# gnode.net
KiCad netlist of a schematic drawn in EAGLE
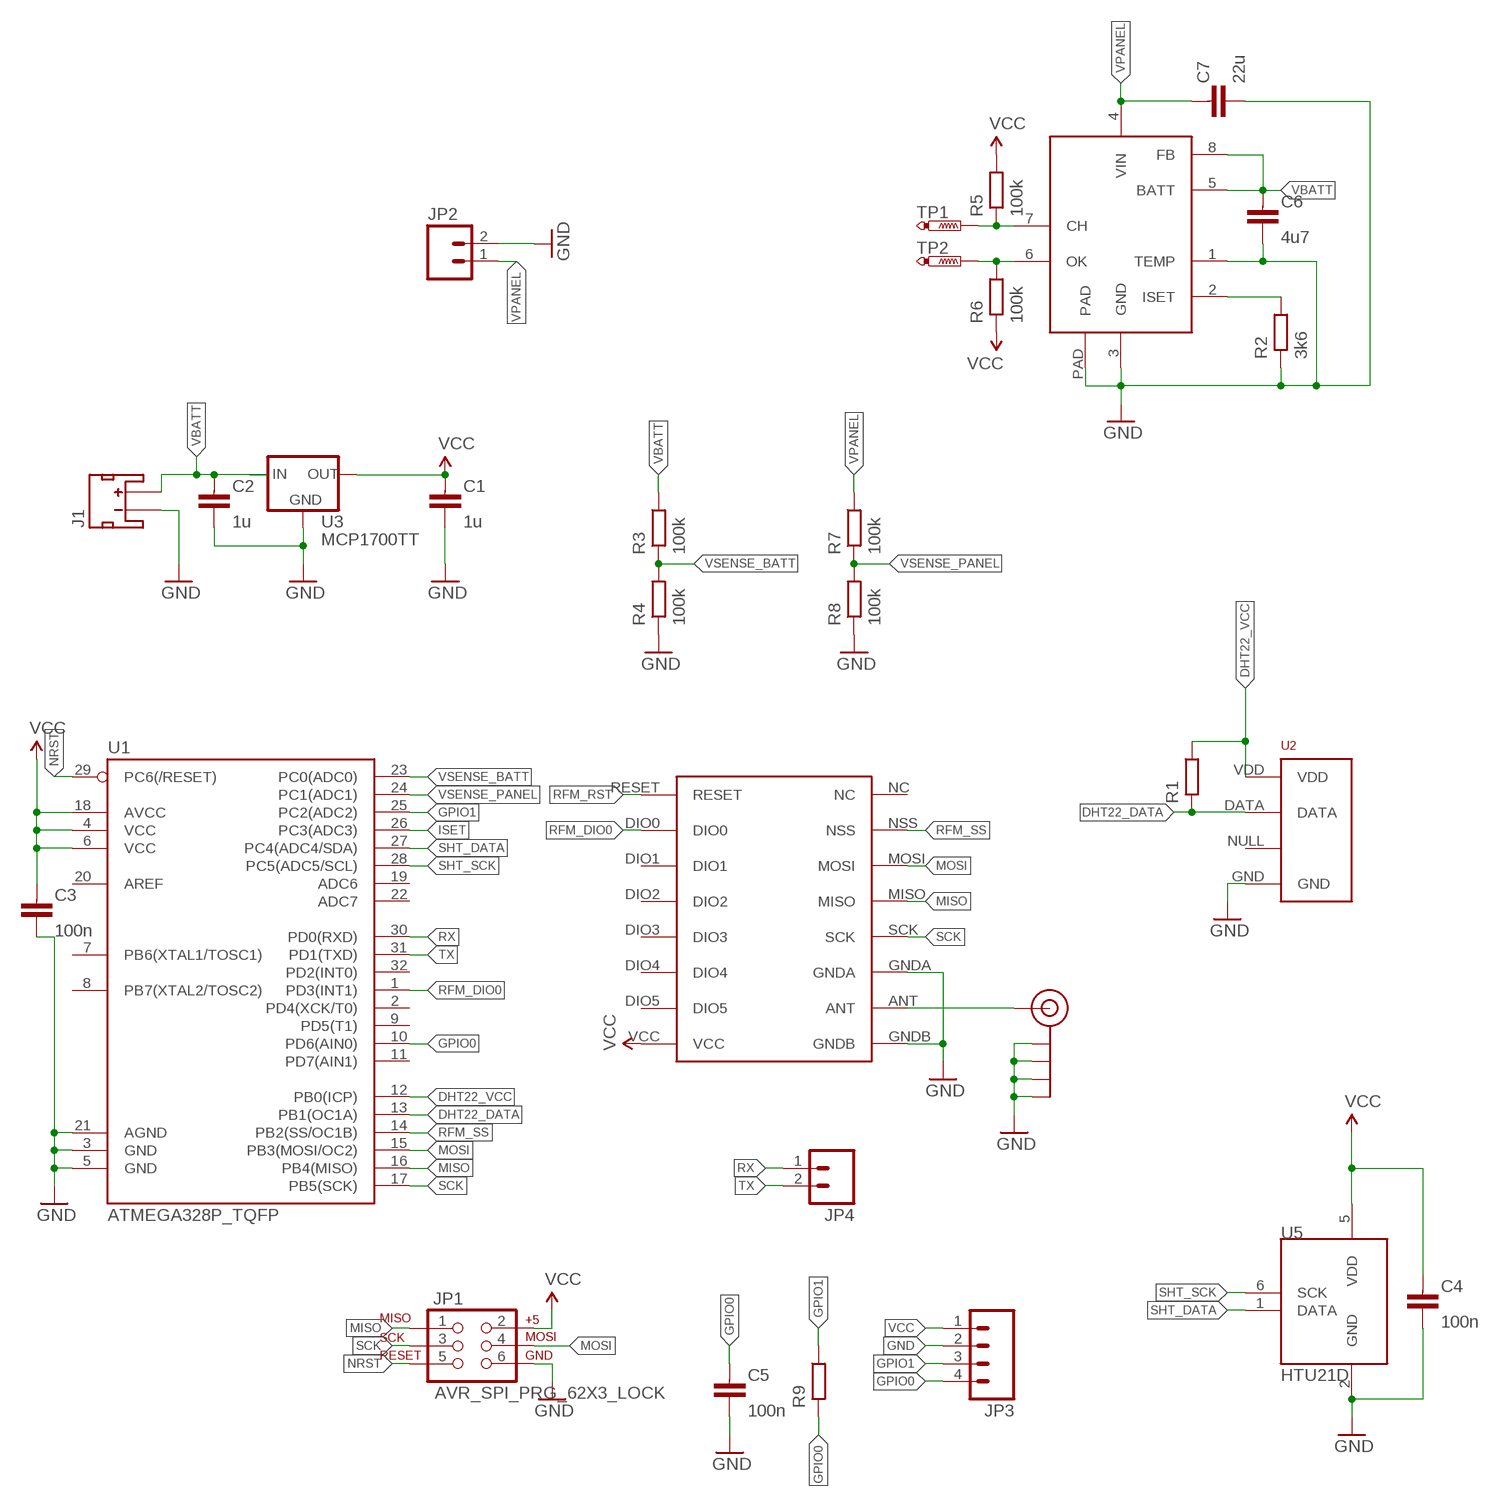
[diagram p0: schematic, sheet 1]

(export (version "E")
  (design (tool "Eeschema 10.0.6"))
  (components
    (comp (ref "C1")
      (value "1u")
      (footprint "eagle-import:C0603-N")
      (libsource (lib "eagle-import") (part "CAPACITOR0603-N"))
    )
    (comp (ref "C2")
      (value "1u")
      (footprint "eagle-import:C0603-N")
      (libsource (lib "eagle-import") (part "CAPACITOR0603-N"))
    )
    (comp (ref "C3")
      (value "100n")
      (footprint "eagle-import:C0603-N")
      (libsource (lib "eagle-import") (part "CAPACITOR0603-N"))
    )
    (comp (ref "C4")
      (value "100n")
      (footprint "eagle-import:C0603-N")
      (libsource (lib "eagle-import") (part "CAPACITOR0603-N"))
    )
    (comp (ref "C5")
      (value "100n")
      (footprint "eagle-import:C0603-N")
      (libsource (lib "eagle-import") (part "CAPACITOR0603-N"))
    )
    (comp (ref "C6")
      (value "4u7")
      (footprint "eagle-import:C0603-N")
      (libsource (lib "eagle-import") (part "CAPACITOR0603-N"))
    )
    (comp (ref "C7")
      (value "22u")
      (footprint "eagle-import:C0603-N")
      (libsource (lib "eagle-import") (part "CAPACITOR0603-N"))
    )
    (comp (ref "J$1")
      (value "SMA_EDGE")
      (footprint "eagle-import:SMA-EDGE")
      (libsource (lib "eagle-import") (part "SMA_EDGE"))
    )
    (comp (ref "J1")
      (value "JST_2MM_MALE_TH")
      (footprint "eagle-import:JST-2-TH")
      (libsource (lib "eagle-import") (part "JST_2MM_MALE_TH"))
    )
    (comp (ref "JP1")
      (value "AVR_SPI_PRG_62X3_LOCK")
      (footprint "eagle-import:2X3_LOCK")
      (libsource (lib "eagle-import") (part "AVR_SPI_PRG_62X3_LOCK"))
    )
    (comp (ref "JP2")
      (value "M02PTH")
      (footprint "eagle-import:1X02")
      (libsource (lib "eagle-import") (part "M02PTH"))
    )
    (comp (ref "JP3")
      (value "M04PTH")
      (footprint "eagle-import:1X04")
      (libsource (lib "eagle-import") (part "M04PTH"))
    )
    (comp (ref "JP4")
      (value "M02PTH")
      (footprint "eagle-import:1X02")
      (libsource (lib "eagle-import") (part "M02PTH"))
    )
    (comp (ref "R1")
      (value "RESISTOR0603-N")
      (footprint "eagle-import:R0603-N")
      (libsource (lib "eagle-import") (part "RESISTOR0603-N"))
    )
    (comp (ref "R2")
      (value "3k6")
      (footprint "eagle-import:R0603-N")
      (libsource (lib "eagle-import") (part "RESISTOR0603-N"))
    )
    (comp (ref "R3")
      (value "100k")
      (footprint "eagle-import:R0603-N")
      (libsource (lib "eagle-import") (part "RESISTOR0603-N"))
    )
    (comp (ref "R4")
      (value "100k")
      (footprint "eagle-import:R0603-N")
      (libsource (lib "eagle-import") (part "RESISTOR0603-N"))
    )
    (comp (ref "R5")
      (value "100k")
      (footprint "eagle-import:R0603-N")
      (libsource (lib "eagle-import") (part "RESISTOR0603-N"))
    )
    (comp (ref "R6")
      (value "100k")
      (footprint "eagle-import:R0603-N")
      (libsource (lib "eagle-import") (part "RESISTOR0603-N"))
    )
    (comp (ref "R7")
      (value "100k")
      (footprint "eagle-import:R0603-N")
      (libsource (lib "eagle-import") (part "RESISTOR0603-N"))
    )
    (comp (ref "R8")
      (value "100k")
      (footprint "eagle-import:R0603-N")
      (libsource (lib "eagle-import") (part "RESISTOR0603-N"))
    )
    (comp (ref "R9")
      (value "RESISTOR0603-N")
      (footprint "eagle-import:R0603-N")
      (libsource (lib "eagle-import") (part "RESISTOR0603-N"))
    )
    (comp (ref "TP1")
      (value "PTR1B1,27")
      (footprint "eagle-import:B1,27")
      (libsource (lib "eagle-import") (part "PTR1B1,27"))
    )
    (comp (ref "TP2")
      (value "PTR1B1,27")
      (footprint "eagle-import:B1,27")
      (libsource (lib "eagle-import") (part "PTR1B1,27"))
    )
    (comp (ref "U$1")
      (value "RFM69HW")
      (footprint "eagle-import:RFM")
      (libsource (lib "eagle-import") (part "RFM69HW"))
    )
    (comp (ref "U1")
      (value "ATMEGA328P_TQFP")
      (footprint "eagle-import:TQFP32-08")
      (libsource (lib "eagle-import") (part "ATMEGA328P_TQFP"))
    )
    (comp (ref "U2")
      (value "RHT03_DHT-22_AM2302")
      (footprint "eagle-import:RHT03_DHT-22")
      (libsource (lib "eagle-import") (part "RHT03_DHT-22_AM2302"))
    )
    (comp (ref "U3")
      (value "MCP1700TT")
      (footprint "eagle-import:SOT23")
      (libsource (lib "eagle-import") (part "MCP1700TT"))
    )
    (comp (ref "U4")
      (value "CN3083")
      (footprint "eagle-import:SO8-PAD")
      (libsource (lib "eagle-import") (part "CN3083"))
    )
    (comp (ref "U5")
      (value "HTU21D")
      (footprint "eagle-import:DFN6-L")
      (libsource (lib "eagle-import") (part "HTU21D"))
    )
  )
  (nets
    (net (code "1") (name "DHT22_DATA") (class "Default")
      (node (ref "R1") (pin "1") (pinfunction "P$1_1") (pintype "passive"))
      (node (ref "U1") (pin "13") (pinfunction "PB1(OC1A)_13") (pintype "bidirectional"))
      (node (ref "U2") (pin "DATA") (pinfunction "DATA_DATA") (pintype "bidirectional"))
    )
    (net (code "2") (name "DHT22_VCC") (class "Default")
      (node (ref "R1") (pin "2") (pinfunction "P$2_2") (pintype "passive"))
      (node (ref "U1") (pin "12") (pinfunction "PB0(ICP)_12") (pintype "bidirectional"))
      (node (ref "U2") (pin "VDD") (pinfunction "VDD_VDD") (pintype "power_in"))
    )
    (net (code "3") (name "GND") (class "Default")
      (node (ref "C1") (pin "2") (pinfunction "2_2") (pintype "passive"))
      (node (ref "C2") (pin "2") (pinfunction "2_2") (pintype "passive"))
      (node (ref "C3") (pin "2") (pinfunction "2_2") (pintype "passive"))
      (node (ref "C4") (pin "2") (pinfunction "2_2") (pintype "passive"))
      (node (ref "C5") (pin "2") (pinfunction "2_2") (pintype "passive"))
      (node (ref "C6") (pin "2") (pinfunction "2_2") (pintype "passive"))
      (node (ref "C7") (pin "2") (pinfunction "2_2") (pintype "passive"))
      (node (ref "J$1") (pin "GND@0") (pinfunction "GND_GND@0") (pintype "bidirectional"))
      (node (ref "J$1") (pin "GND@1") (pinfunction "GND_GND@1") (pintype "bidirectional"))
      (node (ref "J$1") (pin "GND@2") (pinfunction "GND_GND@2") (pintype "bidirectional"))
      (node (ref "J$1") (pin "GND@3") (pinfunction "GND_GND@3") (pintype "bidirectional"))
      (node (ref "J1") (pin "2") (pinfunction "-_2") (pintype "bidirectional"))
      (node (ref "JP1") (pin "6") (pinfunction "6_6") (pintype "passive"))
      (node (ref "JP2") (pin "2") (pinfunction "2_2") (pintype "passive"))
      (node (ref "JP3") (pin "2") (pinfunction "2_2") (pintype "passive"))
      (node (ref "R2") (pin "1") (pinfunction "P$1_1") (pintype "passive"))
      (node (ref "R4") (pin "1") (pinfunction "P$1_1") (pintype "passive"))
      (node (ref "R8") (pin "1") (pinfunction "P$1_1") (pintype "passive"))
      (node (ref "U$1") (pin "GNDA") (pinfunction "GNDA_GNDA") (pintype "bidirectional"))
      (node (ref "U$1") (pin "GNDB") (pinfunction "GNDB_GNDB") (pintype "bidirectional"))
      (node (ref "U1") (pin "21") (pinfunction "AGND_21") (pintype "bidirectional"))
      (node (ref "U1") (pin "3") (pinfunction "GND_3") (pintype "bidirectional"))
      (node (ref "U1") (pin "5") (pinfunction "GND_5") (pintype "bidirectional"))
      (node (ref "U2") (pin "GND") (pinfunction "GND_GND") (pintype "power_in"))
      (node (ref "U3") (pin "1") (pinfunction "GND_1") (pintype "input"))
      (node (ref "U4") (pin "1") (pinfunction "TEMP_1") (pintype "bidirectional"))
      (node (ref "U4") (pin "3") (pinfunction "GND_3") (pintype "bidirectional"))
      (node (ref "U4") (pin "PAD") (pinfunction "PAD_PAD") (pintype "bidirectional"))
      (node (ref "U5") (pin "2") (pinfunction "GND_2") (pintype "power_in"))
    )
    (net (code "4") (name "GPIO0") (class "Default")
      (node (ref "C5") (pin "1") (pinfunction "1_1") (pintype "passive"))
      (node (ref "JP3") (pin "4") (pinfunction "4_4") (pintype "passive"))
      (node (ref "R9") (pin "1") (pinfunction "P$1_1") (pintype "passive"))
      (node (ref "U1") (pin "10") (pinfunction "PD6(AIN0)_10") (pintype "bidirectional"))
    )
    (net (code "5") (name "GPIO1") (class "Default")
      (node (ref "JP3") (pin "3") (pinfunction "3_3") (pintype "passive"))
      (node (ref "R9") (pin "2") (pinfunction "P$2_2") (pintype "passive"))
      (node (ref "U1") (pin "25") (pinfunction "PC2(ADC2)_25") (pintype "bidirectional"))
    )
    (net (code "6") (name "ISET") (class "Default")
      (node (ref "R2") (pin "2") (pinfunction "P$2_2") (pintype "passive"))
      (node (ref "U1") (pin "26") (pinfunction "PC3(ADC3)_26") (pintype "bidirectional"))
      (node (ref "U4") (pin "2") (pinfunction "ISET_2") (pintype "bidirectional"))
    )
    (net (code "7") (name "MISO") (class "Default")
      (node (ref "JP1") (pin "1") (pinfunction "1_1") (pintype "passive"))
      (node (ref "U$1") (pin "MISO") (pinfunction "MISO_MISO") (pintype "bidirectional"))
      (node (ref "U1") (pin "16") (pinfunction "PB4(MISO)_16") (pintype "bidirectional"))
    )
    (net (code "8") (name "MOSI") (class "Default")
      (node (ref "JP1") (pin "4") (pinfunction "4_4") (pintype "passive"))
      (node (ref "U$1") (pin "MOSI") (pinfunction "MOSI_MOSI") (pintype "bidirectional"))
      (node (ref "U1") (pin "15") (pinfunction "PB3(MOSI/OC2)_15") (pintype "bidirectional"))
    )
    (net (code "9") (name "NRST") (class "Default")
      (node (ref "JP1") (pin "5") (pinfunction "5_5") (pintype "passive"))
      (node (ref "U1") (pin "29") (pinfunction "PC6(/RESET)_29") (pintype "bidirectional"))
    )
    (net (code "10") (name "Net-(J$1-SIGNAL)") (class "Default")
      (node (ref "J$1") (pin "SIG") (pinfunction "SIGNAL_SIG") (pintype "bidirectional"))
      (node (ref "U$1") (pin "ANT") (pinfunction "ANT_ANT") (pintype "bidirectional"))
    )
    (net (code "11") (name "Net-(R5-P$1)") (class "Default")
      (node (ref "R5") (pin "1") (pinfunction "P$1_1") (pintype "passive"))
      (node (ref "TP1") (pin "TP") (pinfunction "TP_TP") (pintype "input"))
      (node (ref "U4") (pin "7") (pinfunction "CH_7") (pintype "bidirectional"))
    )
    (net (code "12") (name "Net-(R6-P$2)") (class "Default")
      (node (ref "R6") (pin "2") (pinfunction "P$2_2") (pintype "passive"))
      (node (ref "TP2") (pin "TP") (pinfunction "TP_TP") (pintype "input"))
      (node (ref "U4") (pin "6") (pinfunction "OK_6") (pintype "bidirectional"))
    )
    (net (code "13") (name "RFM_DIO0") (class "Default")
      (node (ref "U$1") (pin "DIO0") (pinfunction "DIO0_DIO0") (pintype "bidirectional"))
      (node (ref "U1") (pin "1") (pinfunction "PD3(INT1)_1") (pintype "bidirectional"))
    )
    (net (code "14") (name "RFM_RST") (class "Default")
      (node (ref "U$1") (pin "RESET") (pinfunction "RESET_RESET") (pintype "bidirectional"))
    )
    (net (code "15") (name "RFM_SS") (class "Default")
      (node (ref "U$1") (pin "NSS") (pinfunction "NSS_NSS") (pintype "bidirectional"))
      (node (ref "U1") (pin "14") (pinfunction "PB2(SS/OC1B)_14") (pintype "bidirectional"))
    )
    (net (code "16") (name "RX") (class "Default")
      (node (ref "JP4") (pin "1") (pinfunction "1_1") (pintype "passive"))
      (node (ref "U1") (pin "30") (pinfunction "PD0(RXD)_30") (pintype "bidirectional"))
    )
    (net (code "17") (name "SCK") (class "Default")
      (node (ref "JP1") (pin "3") (pinfunction "3_3") (pintype "passive"))
      (node (ref "U$1") (pin "SCK") (pinfunction "SCK_SCK") (pintype "bidirectional"))
      (node (ref "U1") (pin "17") (pinfunction "PB5(SCK)_17") (pintype "bidirectional"))
    )
    (net (code "18") (name "SHT_DATA") (class "Default")
      (node (ref "U1") (pin "27") (pinfunction "PC4(ADC4/SDA)_27") (pintype "bidirectional"))
      (node (ref "U5") (pin "1") (pinfunction "DATA_1") (pintype "bidirectional"))
    )
    (net (code "19") (name "SHT_SCK") (class "Default")
      (node (ref "U1") (pin "28") (pinfunction "PC5(ADC5/SCL)_28") (pintype "bidirectional"))
      (node (ref "U5") (pin "6") (pinfunction "SCK_6") (pintype "input"))
    )
    (net (code "20") (name "TX") (class "Default")
      (node (ref "JP4") (pin "2") (pinfunction "2_2") (pintype "passive"))
      (node (ref "U1") (pin "31") (pinfunction "PD1(TXD)_31") (pintype "bidirectional"))
    )
    (net (code "21") (name "VBATT") (class "Default")
      (node (ref "C2") (pin "1") (pinfunction "1_1") (pintype "passive"))
      (node (ref "C6") (pin "1") (pinfunction "1_1") (pintype "passive"))
      (node (ref "J1") (pin "1") (pinfunction "+_1") (pintype "bidirectional"))
      (node (ref "R3") (pin "2") (pinfunction "P$2_2") (pintype "passive"))
      (node (ref "U3") (pin "3") (pinfunction "IN_3") (pintype "input"))
      (node (ref "U4") (pin "5") (pinfunction "BATT_5") (pintype "bidirectional"))
      (node (ref "U4") (pin "8") (pinfunction "FB_8") (pintype "bidirectional"))
    )
    (net (code "22") (name "VCC") (class "Default")
      (node (ref "C1") (pin "1") (pinfunction "1_1") (pintype "passive"))
      (node (ref "C3") (pin "1") (pinfunction "1_1") (pintype "passive"))
      (node (ref "C4") (pin "1") (pinfunction "1_1") (pintype "passive"))
      (node (ref "JP1") (pin "2") (pinfunction "2_2") (pintype "passive"))
      (node (ref "JP3") (pin "1") (pinfunction "1_1") (pintype "passive"))
      (node (ref "R5") (pin "2") (pinfunction "P$2_2") (pintype "passive"))
      (node (ref "R6") (pin "1") (pinfunction "P$1_1") (pintype "passive"))
      (node (ref "U$1") (pin "VCC") (pinfunction "VCC_VCC") (pintype "bidirectional"))
      (node (ref "U1") (pin "18") (pinfunction "AVCC_18") (pintype "bidirectional"))
      (node (ref "U1") (pin "4") (pinfunction "VCC_4") (pintype "bidirectional"))
      (node (ref "U1") (pin "6") (pinfunction "VCC_6") (pintype "bidirectional"))
      (node (ref "U3") (pin "2") (pinfunction "OUT_2") (pintype "passive"))
      (node (ref "U5") (pin "5") (pinfunction "VDD_5") (pintype "power_in"))
    )
    (net (code "23") (name "VPANEL") (class "Default")
      (node (ref "C7") (pin "1") (pinfunction "1_1") (pintype "passive"))
      (node (ref "JP2") (pin "1") (pinfunction "1_1") (pintype "passive"))
      (node (ref "R7") (pin "2") (pinfunction "P$2_2") (pintype "passive"))
      (node (ref "U4") (pin "4") (pinfunction "VIN_4") (pintype "bidirectional"))
    )
    (net (code "24") (name "VSENSE_BATT") (class "Default")
      (node (ref "R3") (pin "1") (pinfunction "P$1_1") (pintype "passive"))
      (node (ref "R4") (pin "2") (pinfunction "P$2_2") (pintype "passive"))
      (node (ref "U1") (pin "23") (pinfunction "PC0(ADC0)_23") (pintype "bidirectional"))
    )
    (net (code "25") (name "VSENSE_PANEL") (class "Default")
      (node (ref "R7") (pin "1") (pinfunction "P$1_1") (pintype "passive"))
      (node (ref "R8") (pin "2") (pinfunction "P$2_2") (pintype "passive"))
      (node (ref "U1") (pin "24") (pinfunction "PC1(ADC1)_24") (pintype "bidirectional"))
    )
    (net (code "26") (name "unconnected-(U$1-PadDIO1)") (class "Default")
      (node (ref "U$1") (pin "DIO1") (pinfunction "DIO1_DIO1") (pintype "bidirectional"))
    )
    (net (code "27") (name "unconnected-(U$1-PadDIO2)") (class "Default")
      (node (ref "U$1") (pin "DIO2") (pinfunction "DIO2_DIO2") (pintype "bidirectional"))
    )
    (net (code "28") (name "unconnected-(U$1-PadDIO3)") (class "Default")
      (node (ref "U$1") (pin "DIO3") (pinfunction "DIO3_DIO3") (pintype "bidirectional"))
    )
    (net (code "29") (name "unconnected-(U$1-PadDIO4)") (class "Default")
      (node (ref "U$1") (pin "DIO4") (pinfunction "DIO4_DIO4") (pintype "bidirectional"))
    )
    (net (code "30") (name "unconnected-(U$1-PadDIO5)") (class "Default")
      (node (ref "U$1") (pin "DIO5") (pinfunction "DIO5_DIO5") (pintype "bidirectional"))
    )
    (net (code "31") (name "unconnected-(U$1-PadNC)") (class "Default")
      (node (ref "U$1") (pin "NC") (pinfunction "NC_NC") (pintype "bidirectional"))
    )
    (net (code "32") (name "unconnected-(U1-ADC6-Pad19)") (class "Default")
      (node (ref "U1") (pin "19") (pinfunction "ADC6_19") (pintype "bidirectional"))
    )
    (net (code "33") (name "unconnected-(U1-ADC7-Pad22)") (class "Default")
      (node (ref "U1") (pin "22") (pinfunction "ADC7_22") (pintype "bidirectional"))
    )
    (net (code "34") (name "unconnected-(U1-AREF-Pad20)") (class "Default")
      (node (ref "U1") (pin "20") (pinfunction "AREF_20") (pintype "bidirectional"))
    )
    (net (code "35") (name "unconnected-(U1-PB6(XTAL1{slash}TOSC1)-Pad7)") (class "Default")
      (node (ref "U1") (pin "7") (pinfunction "PB6(XTAL1/TOSC1)_7") (pintype "bidirectional"))
    )
    (net (code "36") (name "unconnected-(U1-PB7(XTAL2{slash}TOSC2)-Pad8)") (class "Default")
      (node (ref "U1") (pin "8") (pinfunction "PB7(XTAL2/TOSC2)_8") (pintype "bidirectional"))
    )
    (net (code "37") (name "unconnected-(U1-PD2(INT0)-Pad32)") (class "Default")
      (node (ref "U1") (pin "32") (pinfunction "PD2(INT0)_32") (pintype "bidirectional"))
    )
    (net (code "38") (name "unconnected-(U1-PD4(XCK{slash}T0)-Pad2)") (class "Default")
      (node (ref "U1") (pin "2") (pinfunction "PD4(XCK/T0)_2") (pintype "bidirectional"))
    )
    (net (code "39") (name "unconnected-(U1-PD5(T1)-Pad9)") (class "Default")
      (node (ref "U1") (pin "9") (pinfunction "PD5(T1)_9") (pintype "bidirectional"))
    )
    (net (code "40") (name "unconnected-(U1-PD7(AIN1)-Pad11)") (class "Default")
      (node (ref "U1") (pin "11") (pinfunction "PD7(AIN1)_11") (pintype "bidirectional"))
    )
    (net (code "41") (name "unconnected-(U2-PadNULL)") (class "Default")
      (node (ref "U2") (pin "NULL") (pinfunction "NULL_NULL") (pintype "no_connect"))
    )
  )
)
